# 2019_10_ELEV_18_IO.net
KiCad netlist of a schematic drawn in Altium Designer
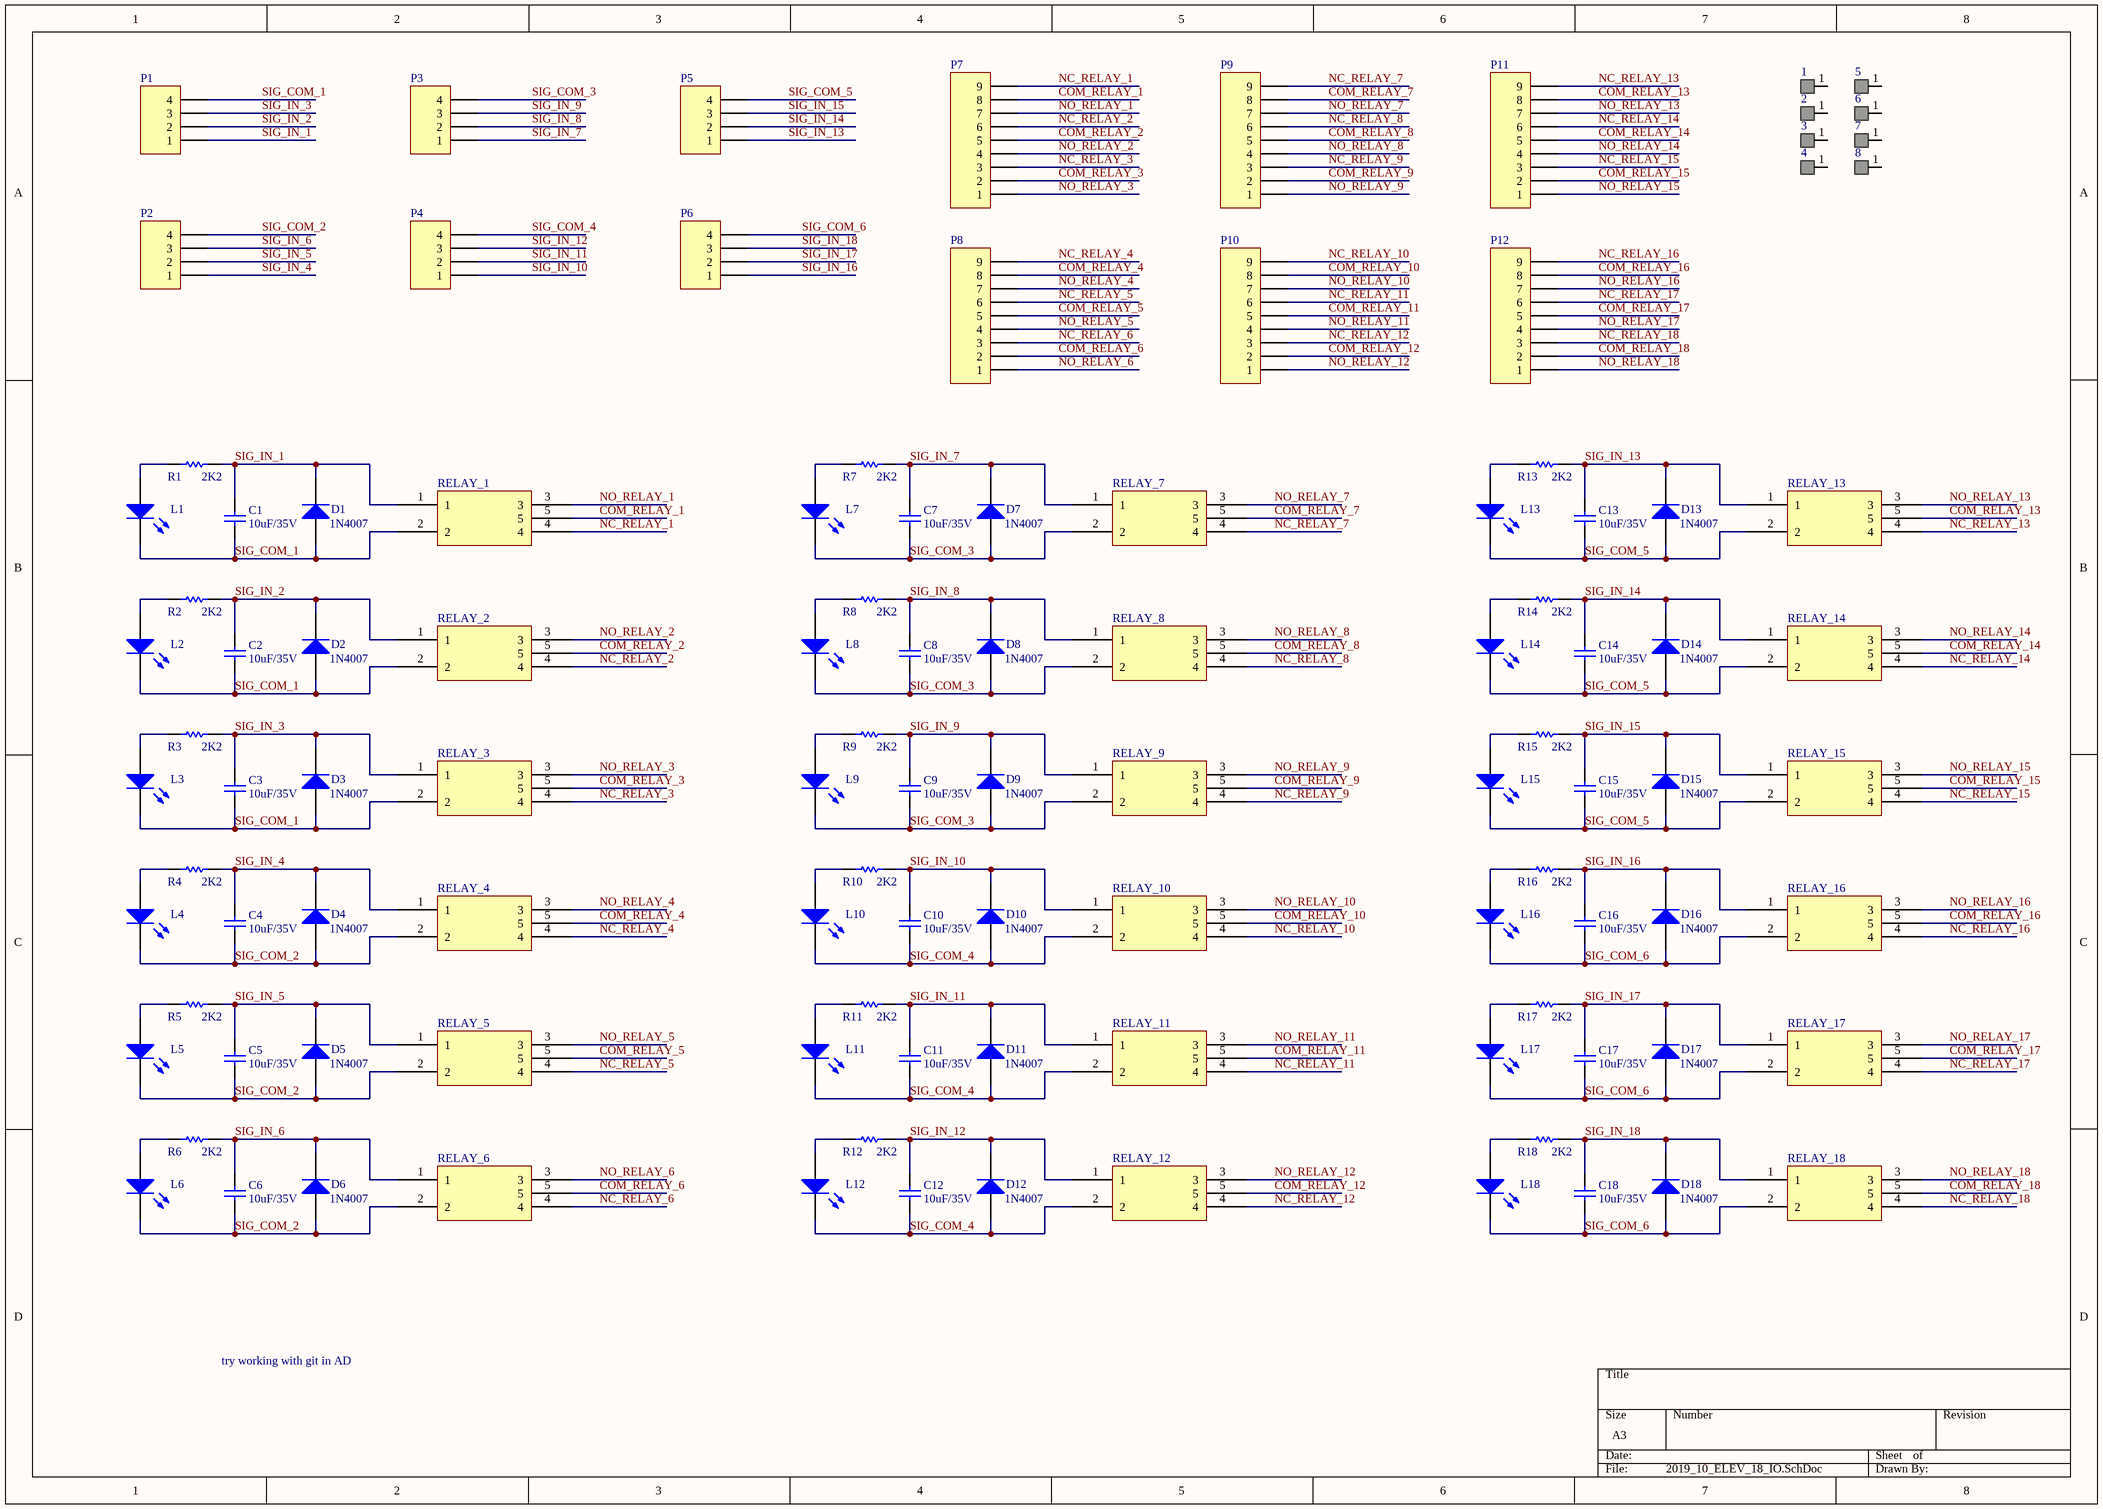
[diagram p0: 2019_10_ELEV_18_IO.SchDoc]

(export (version "E")
  (design (tool "Eeschema 10.0.6"))
  (components
    (comp (ref "1")
      (value "LOVIT_1")
      (footprint "VIT")
      (libsource (lib "2019_10_ELEV_18_IO") (part "LOVIT_1"))
    )
    (comp (ref "2")
      (value "LOVIT_1")
      (footprint "VIT")
      (libsource (lib "2019_10_ELEV_18_IO") (part "LOVIT_1"))
    )
    (comp (ref "3")
      (value "LOVIT_1")
      (footprint "VIT")
      (libsource (lib "2019_10_ELEV_18_IO") (part "LOVIT_1"))
    )
    (comp (ref "4")
      (value "LOVIT_1")
      (footprint "VIT")
      (libsource (lib "2019_10_ELEV_18_IO") (part "LOVIT_1"))
    )
    (comp (ref "5")
      (value "LOVIT_1")
      (footprint "VIT")
      (libsource (lib "2019_10_ELEV_18_IO") (part "LOVIT_1"))
    )
    (comp (ref "6")
      (value "LOVIT_1")
      (footprint "VIT")
      (libsource (lib "2019_10_ELEV_18_IO") (part "LOVIT_1"))
    )
    (comp (ref "7")
      (value "LOVIT_1")
      (footprint "VIT")
      (libsource (lib "2019_10_ELEV_18_IO") (part "LOVIT_1"))
    )
    (comp (ref "8")
      (value "LOVIT_1")
      (footprint "VIT")
      (libsource (lib "2019_10_ELEV_18_IO") (part "LOVIT_1"))
    )
    (comp (ref "C1")
      (value "10uF/35V")
      (footprint "C1210C106M6PACTU")
      (description "Multilayer Ceramic Capacitors MLCC - SMD/SMT 35V 10uF X5R 1210 20%")
      (fields (field (name "Comment") "Capacitor"))
      (libsource (lib "ICENTER_V3_2019_SCHLIB") (part "C1210C106M6PAC"))
    )
    (comp (ref "C2")
      (value "10uF/35V")
      (footprint "C1210C106M6PACTU")
      (description "Multilayer Ceramic Capacitors MLCC - SMD/SMT 35V 10uF X5R 1210 20%")
      (fields (field (name "Comment") "Capacitor"))
      (libsource (lib "ICENTER_V3_2019_SCHLIB") (part "C1210C106M6PAC"))
    )
    (comp (ref "C3")
      (value "10uF/35V")
      (footprint "C1210C106M6PACTU")
      (description "Multilayer Ceramic Capacitors MLCC - SMD/SMT 35V 10uF X5R 1210 20%")
      (fields (field (name "Comment") "Capacitor"))
      (libsource (lib "ICENTER_V3_2019_SCHLIB") (part "C1210C106M6PAC"))
    )
    (comp (ref "C4")
      (value "10uF/35V")
      (footprint "C1210C106M6PACTU")
      (description "Multilayer Ceramic Capacitors MLCC - SMD/SMT 35V 10uF X5R 1210 20%")
      (fields (field (name "Comment") "Capacitor"))
      (libsource (lib "ICENTER_V3_2019_SCHLIB") (part "C1210C106M6PAC"))
    )
    (comp (ref "C5")
      (value "10uF/35V")
      (footprint "C1210C106M6PACTU")
      (description "Multilayer Ceramic Capacitors MLCC - SMD/SMT 35V 10uF X5R 1210 20%")
      (fields (field (name "Comment") "Capacitor"))
      (libsource (lib "ICENTER_V3_2019_SCHLIB") (part "C1210C106M6PAC"))
    )
    (comp (ref "C6")
      (value "10uF/35V")
      (footprint "C1210C106M6PACTU")
      (description "Multilayer Ceramic Capacitors MLCC - SMD/SMT 35V 10uF X5R 1210 20%")
      (fields (field (name "Comment") "Capacitor"))
      (libsource (lib "ICENTER_V3_2019_SCHLIB") (part "C1210C106M6PAC"))
    )
    (comp (ref "C7")
      (value "10uF/35V")
      (footprint "C1210C106M6PACTU")
      (description "Multilayer Ceramic Capacitors MLCC - SMD/SMT 35V 10uF X5R 1210 20%")
      (fields (field (name "Comment") "Capacitor"))
      (libsource (lib "ICENTER_V3_2019_SCHLIB") (part "C1210C106M6PAC"))
    )
    (comp (ref "C8")
      (value "10uF/35V")
      (footprint "C1210C106M6PACTU")
      (description "Multilayer Ceramic Capacitors MLCC - SMD/SMT 35V 10uF X5R 1210 20%")
      (fields (field (name "Comment") "Capacitor"))
      (libsource (lib "ICENTER_V3_2019_SCHLIB") (part "C1210C106M6PAC"))
    )
    (comp (ref "C9")
      (value "10uF/35V")
      (footprint "C1210C106M6PACTU")
      (description "Multilayer Ceramic Capacitors MLCC - SMD/SMT 35V 10uF X5R 1210 20%")
      (fields (field (name "Comment") "Capacitor"))
      (libsource (lib "ICENTER_V3_2019_SCHLIB") (part "C1210C106M6PAC"))
    )
    (comp (ref "C10")
      (value "10uF/35V")
      (footprint "C1210C106M6PACTU")
      (description "Multilayer Ceramic Capacitors MLCC - SMD/SMT 35V 10uF X5R 1210 20%")
      (fields (field (name "Comment") "Capacitor"))
      (libsource (lib "ICENTER_V3_2019_SCHLIB") (part "C1210C106M6PAC"))
    )
    (comp (ref "C11")
      (value "10uF/35V")
      (footprint "C1210C106M6PACTU")
      (description "Multilayer Ceramic Capacitors MLCC - SMD/SMT 35V 10uF X5R 1210 20%")
      (fields (field (name "Comment") "Capacitor"))
      (libsource (lib "ICENTER_V3_2019_SCHLIB") (part "C1210C106M6PAC"))
    )
    (comp (ref "C12")
      (value "10uF/35V")
      (footprint "C1210C106M6PACTU")
      (description "Multilayer Ceramic Capacitors MLCC - SMD/SMT 35V 10uF X5R 1210 20%")
      (fields (field (name "Comment") "Capacitor"))
      (libsource (lib "ICENTER_V3_2019_SCHLIB") (part "C1210C106M6PAC"))
    )
    (comp (ref "C13")
      (value "10uF/35V")
      (footprint "C1210C106M6PACTU")
      (description "Multilayer Ceramic Capacitors MLCC - SMD/SMT 35V 10uF X5R 1210 20%")
      (fields (field (name "Comment") "Capacitor"))
      (libsource (lib "ICENTER_V3_2019_SCHLIB") (part "C1210C106M6PAC"))
    )
    (comp (ref "C14")
      (value "10uF/35V")
      (footprint "C1210C106M6PACTU")
      (description "Multilayer Ceramic Capacitors MLCC - SMD/SMT 35V 10uF X5R 1210 20%")
      (fields (field (name "Comment") "Capacitor"))
      (libsource (lib "ICENTER_V3_2019_SCHLIB") (part "C1210C106M6PAC"))
    )
    (comp (ref "C15")
      (value "10uF/35V")
      (footprint "C1210C106M6PACTU")
      (description "Multilayer Ceramic Capacitors MLCC - SMD/SMT 35V 10uF X5R 1210 20%")
      (fields (field (name "Comment") "Capacitor"))
      (libsource (lib "ICENTER_V3_2019_SCHLIB") (part "C1210C106M6PAC"))
    )
    (comp (ref "C16")
      (value "10uF/35V")
      (footprint "C1210C106M6PACTU")
      (description "Multilayer Ceramic Capacitors MLCC - SMD/SMT 35V 10uF X5R 1210 20%")
      (fields (field (name "Comment") "Capacitor"))
      (libsource (lib "ICENTER_V3_2019_SCHLIB") (part "C1210C106M6PAC"))
    )
    (comp (ref "C17")
      (value "10uF/35V")
      (footprint "C1210C106M6PACTU")
      (description "Multilayer Ceramic Capacitors MLCC - SMD/SMT 35V 10uF X5R 1210 20%")
      (fields (field (name "Comment") "Capacitor"))
      (libsource (lib "ICENTER_V3_2019_SCHLIB") (part "C1210C106M6PAC"))
    )
    (comp (ref "C18")
      (value "10uF/35V")
      (footprint "C1210C106M6PACTU")
      (description "Multilayer Ceramic Capacitors MLCC - SMD/SMT 35V 10uF X5R 1210 20%")
      (fields (field (name "Comment") "Capacitor"))
      (libsource (lib "ICENTER_V3_2019_SCHLIB") (part "C1210C106M6PAC"))
    )
    (comp (ref "D1")
      (value "1N4007")
      (footprint "DO-214AC")
      (description "Diode Rectifiers 1.5 Amp 1000 Volt")
      (libsource (lib "ICENTER_V3_2019_SCHLIB") (part "BYG21M-E3/TR"))
    )
    (comp (ref "D2")
      (value "1N4007")
      (footprint "DO-214AC")
      (description "Diode Rectifiers 1.5 Amp 1000 Volt")
      (libsource (lib "ICENTER_V3_2019_SCHLIB") (part "BYG21M-E3/TR"))
    )
    (comp (ref "D3")
      (value "1N4007")
      (footprint "DO-214AC")
      (description "Diode Rectifiers 1.5 Amp 1000 Volt")
      (libsource (lib "ICENTER_V3_2019_SCHLIB") (part "BYG21M-E3/TR"))
    )
    (comp (ref "D4")
      (value "1N4007")
      (footprint "DO-214AC")
      (description "Diode Rectifiers 1.5 Amp 1000 Volt")
      (libsource (lib "ICENTER_V3_2019_SCHLIB") (part "BYG21M-E3/TR"))
    )
    (comp (ref "D5")
      (value "1N4007")
      (footprint "DO-214AC")
      (description "Diode Rectifiers 1.5 Amp 1000 Volt")
      (libsource (lib "ICENTER_V3_2019_SCHLIB") (part "BYG21M-E3/TR"))
    )
    (comp (ref "D6")
      (value "1N4007")
      (footprint "DO-214AC")
      (description "Diode Rectifiers 1.5 Amp 1000 Volt")
      (libsource (lib "ICENTER_V3_2019_SCHLIB") (part "BYG21M-E3/TR"))
    )
    (comp (ref "D7")
      (value "1N4007")
      (footprint "DO-214AC")
      (description "Diode Rectifiers 1.5 Amp 1000 Volt")
      (libsource (lib "ICENTER_V3_2019_SCHLIB") (part "BYG21M-E3/TR"))
    )
    (comp (ref "D8")
      (value "1N4007")
      (footprint "DO-214AC")
      (description "Diode Rectifiers 1.5 Amp 1000 Volt")
      (libsource (lib "ICENTER_V3_2019_SCHLIB") (part "BYG21M-E3/TR"))
    )
    (comp (ref "D9")
      (value "1N4007")
      (footprint "DO-214AC")
      (description "Diode Rectifiers 1.5 Amp 1000 Volt")
      (libsource (lib "ICENTER_V3_2019_SCHLIB") (part "BYG21M-E3/TR"))
    )
    (comp (ref "D10")
      (value "1N4007")
      (footprint "DO-214AC")
      (description "Diode Rectifiers 1.5 Amp 1000 Volt")
      (libsource (lib "ICENTER_V3_2019_SCHLIB") (part "BYG21M-E3/TR"))
    )
    (comp (ref "D11")
      (value "1N4007")
      (footprint "DO-214AC")
      (description "Diode Rectifiers 1.5 Amp 1000 Volt")
      (libsource (lib "ICENTER_V3_2019_SCHLIB") (part "BYG21M-E3/TR"))
    )
    (comp (ref "D12")
      (value "1N4007")
      (footprint "DO-214AC")
      (description "Diode Rectifiers 1.5 Amp 1000 Volt")
      (libsource (lib "ICENTER_V3_2019_SCHLIB") (part "BYG21M-E3/TR"))
    )
    (comp (ref "D13")
      (value "1N4007")
      (footprint "DO-214AC")
      (description "Diode Rectifiers 1.5 Amp 1000 Volt")
      (libsource (lib "ICENTER_V3_2019_SCHLIB") (part "BYG21M-E3/TR"))
    )
    (comp (ref "D14")
      (value "1N4007")
      (footprint "DO-214AC")
      (description "Diode Rectifiers 1.5 Amp 1000 Volt")
      (libsource (lib "ICENTER_V3_2019_SCHLIB") (part "BYG21M-E3/TR"))
    )
    (comp (ref "D15")
      (value "1N4007")
      (footprint "DO-214AC")
      (description "Diode Rectifiers 1.5 Amp 1000 Volt")
      (libsource (lib "ICENTER_V3_2019_SCHLIB") (part "BYG21M-E3/TR"))
    )
    (comp (ref "D16")
      (value "1N4007")
      (footprint "DO-214AC")
      (description "Diode Rectifiers 1.5 Amp 1000 Volt")
      (libsource (lib "ICENTER_V3_2019_SCHLIB") (part "BYG21M-E3/TR"))
    )
    (comp (ref "D17")
      (value "1N4007")
      (footprint "DO-214AC")
      (description "Diode Rectifiers 1.5 Amp 1000 Volt")
      (libsource (lib "ICENTER_V3_2019_SCHLIB") (part "BYG21M-E3/TR"))
    )
    (comp (ref "D18")
      (value "1N4007")
      (footprint "DO-214AC")
      (description "Diode Rectifiers 1.5 Amp 1000 Volt")
      (libsource (lib "ICENTER_V3_2019_SCHLIB") (part "BYG21M-E3/TR"))
    )
    (comp (ref "L1")
      (value "LED0")
      (footprint "LED_3MM")
      (description "Typical INFRARED GaAs LED")
      (fields (field (name "PUBLISHER") "Altium Limited"))
      (libsource (lib "Miscellaneous Devices") (part "LED0"))
    )
    (comp (ref "L2")
      (value "LED0")
      (footprint "LED_3MM")
      (description "Typical INFRARED GaAs LED")
      (fields (field (name "PUBLISHER") "Altium Limited"))
      (libsource (lib "Miscellaneous Devices") (part "LED0"))
    )
    (comp (ref "L3")
      (value "LED0")
      (footprint "LED_3MM")
      (description "Typical INFRARED GaAs LED")
      (fields (field (name "PUBLISHER") "Altium Limited"))
      (libsource (lib "Miscellaneous Devices") (part "LED0"))
    )
    (comp (ref "L4")
      (value "LED0")
      (footprint "LED_3MM")
      (description "Typical INFRARED GaAs LED")
      (fields (field (name "PUBLISHER") "Altium Limited"))
      (libsource (lib "Miscellaneous Devices") (part "LED0"))
    )
    (comp (ref "L5")
      (value "LED0")
      (footprint "LED_3MM")
      (description "Typical INFRARED GaAs LED")
      (fields (field (name "PUBLISHER") "Altium Limited"))
      (libsource (lib "Miscellaneous Devices") (part "LED0"))
    )
    (comp (ref "L6")
      (value "LED0")
      (footprint "LED_3MM")
      (description "Typical INFRARED GaAs LED")
      (fields (field (name "PUBLISHER") "Altium Limited"))
      (libsource (lib "Miscellaneous Devices") (part "LED0"))
    )
    (comp (ref "L7")
      (value "LED0")
      (footprint "LED_3MM")
      (description "Typical INFRARED GaAs LED")
      (fields (field (name "PUBLISHER") "Altium Limited"))
      (libsource (lib "Miscellaneous Devices") (part "LED0"))
    )
    (comp (ref "L8")
      (value "LED0")
      (footprint "LED_3MM")
      (description "Typical INFRARED GaAs LED")
      (fields (field (name "PUBLISHER") "Altium Limited"))
      (libsource (lib "Miscellaneous Devices") (part "LED0"))
    )
    (comp (ref "L9")
      (value "LED0")
      (footprint "LED_3MM")
      (description "Typical INFRARED GaAs LED")
      (fields (field (name "PUBLISHER") "Altium Limited"))
      (libsource (lib "Miscellaneous Devices") (part "LED0"))
    )
    (comp (ref "L10")
      (value "LED0")
      (footprint "LED_3MM")
      (description "Typical INFRARED GaAs LED")
      (fields (field (name "PUBLISHER") "Altium Limited"))
      (libsource (lib "Miscellaneous Devices") (part "LED0"))
    )
    (comp (ref "L11")
      (value "LED0")
      (footprint "LED_3MM")
      (description "Typical INFRARED GaAs LED")
      (fields (field (name "PUBLISHER") "Altium Limited"))
      (libsource (lib "Miscellaneous Devices") (part "LED0"))
    )
    (comp (ref "L12")
      (value "LED0")
      (footprint "LED_3MM")
      (description "Typical INFRARED GaAs LED")
      (fields (field (name "PUBLISHER") "Altium Limited"))
      (libsource (lib "Miscellaneous Devices") (part "LED0"))
    )
    (comp (ref "L13")
      (value "LED0")
      (footprint "LED_3MM")
      (description "Typical INFRARED GaAs LED")
      (fields (field (name "PUBLISHER") "Altium Limited"))
      (libsource (lib "Miscellaneous Devices") (part "LED0"))
    )
    (comp (ref "L14")
      (value "LED0")
      (footprint "LED_3MM")
      (description "Typical INFRARED GaAs LED")
      (fields (field (name "PUBLISHER") "Altium Limited"))
      (libsource (lib "Miscellaneous Devices") (part "LED0"))
    )
    (comp (ref "L15")
      (value "LED0")
      (footprint "LED_3MM")
      (description "Typical INFRARED GaAs LED")
      (fields (field (name "PUBLISHER") "Altium Limited"))
      (libsource (lib "Miscellaneous Devices") (part "LED0"))
    )
    (comp (ref "L16")
      (value "LED0")
      (footprint "LED_3MM")
      (description "Typical INFRARED GaAs LED")
      (fields (field (name "PUBLISHER") "Altium Limited"))
      (libsource (lib "Miscellaneous Devices") (part "LED0"))
    )
    (comp (ref "L17")
      (value "LED0")
      (footprint "LED_3MM")
      (description "Typical INFRARED GaAs LED")
      (fields (field (name "PUBLISHER") "Altium Limited"))
      (libsource (lib "Miscellaneous Devices") (part "LED0"))
    )
    (comp (ref "L18")
      (value "LED0")
      (footprint "LED_3MM")
      (description "Typical INFRARED GaAs LED")
      (fields (field (name "PUBLISHER") "Altium Limited"))
      (libsource (lib "Miscellaneous Devices") (part "LED0"))
    )
    (comp (ref "P1")
      (value "Header 4")
      (footprint "TERMINAL_4PIN_381MM")
      (description "Header, 4-Pin")
      (fields (field (name "PUBLISHER") "Altium Limited"))
      (libsource (lib "Miscellaneous Connectors") (part "Header 4"))
    )
    (comp (ref "P2")
      (value "Header 4")
      (footprint "TERMINAL_4PIN_381MM")
      (description "Header, 4-Pin")
      (fields (field (name "PUBLISHER") "Altium Limited"))
      (libsource (lib "Miscellaneous Connectors") (part "Header 4"))
    )
    (comp (ref "P3")
      (value "Header 4")
      (footprint "TERMINAL_4PIN_381MM")
      (description "Header, 4-Pin")
      (fields (field (name "PUBLISHER") "Altium Limited"))
      (libsource (lib "Miscellaneous Connectors") (part "Header 4"))
    )
    (comp (ref "P4")
      (value "Header 4")
      (footprint "TERMINAL_4PIN_381MM")
      (description "Header, 4-Pin")
      (fields (field (name "PUBLISHER") "Altium Limited"))
      (libsource (lib "Miscellaneous Connectors") (part "Header 4"))
    )
    (comp (ref "P5")
      (value "Header 4")
      (footprint "TERMINAL_4PIN_381MM")
      (description "Header, 4-Pin")
      (fields (field (name "PUBLISHER") "Altium Limited"))
      (libsource (lib "Miscellaneous Connectors") (part "Header 4"))
    )
    (comp (ref "P6")
      (value "Header 4")
      (footprint "TERMINAL_4PIN_381MM")
      (description "Header, 4-Pin")
      (fields (field (name "PUBLISHER") "Altium Limited"))
      (libsource (lib "Miscellaneous Connectors") (part "Header 4"))
    )
    (comp (ref "P7")
      (value "Header 9")
      (footprint "TERMINAL_6PIN_381MM")
      (description "Header, 9-Pin")
      (fields (field (name "PUBLISHER") "Altium Limited"))
      (libsource (lib "Miscellaneous Connectors") (part "Header 9"))
    )
    (comp (ref "P8")
      (value "Header 9")
      (footprint "TERMINAL_6PIN_381MM")
      (description "Header, 9-Pin")
      (fields (field (name "PUBLISHER") "Altium Limited"))
      (libsource (lib "Miscellaneous Connectors") (part "Header 9"))
    )
    (comp (ref "P9")
      (value "Header 9")
      (footprint "TERMINAL_6PIN_381MM")
      (description "Header, 9-Pin")
      (fields (field (name "PUBLISHER") "Altium Limited"))
      (libsource (lib "Miscellaneous Connectors") (part "Header 9"))
    )
    (comp (ref "P10")
      (value "Header 9")
      (footprint "TERMINAL_6PIN_381MM")
      (description "Header, 9-Pin")
      (fields (field (name "PUBLISHER") "Altium Limited"))
      (libsource (lib "Miscellaneous Connectors") (part "Header 9"))
    )
    (comp (ref "P11")
      (value "Header 9")
      (footprint "TERMINAL_6PIN_381MM")
      (description "Header, 9-Pin")
      (fields (field (name "PUBLISHER") "Altium Limited"))
      (libsource (lib "Miscellaneous Connectors") (part "Header 9"))
    )
    (comp (ref "P12")
      (value "Header 9")
      (footprint "TERMINAL_6PIN_381MM")
      (description "Header, 9-Pin")
      (fields (field (name "PUBLISHER") "Altium Limited"))
      (libsource (lib "Miscellaneous Connectors") (part "Header 9"))
    )
    (comp (ref "R1")
      (value "2K2")
      (footprint "CRCW080510K0FKEAC")
      (description "Thick Film Resistors - SMD 1K OHM 5%")
      (fields (field (name "Comment") "Resistor"))
      (libsource (lib "ICENTER_V3_2019_SCHLIB") (part "RC0805JR-131KL"))
    )
    (comp (ref "R2")
      (value "2K2")
      (footprint "CRCW080510K0FKEAC")
      (description "Thick Film Resistors - SMD 1K OHM 5%")
      (fields (field (name "Comment") "Resistor"))
      (libsource (lib "ICENTER_V3_2019_SCHLIB") (part "RC0805JR-131KL"))
    )
    (comp (ref "R3")
      (value "2K2")
      (footprint "CRCW080510K0FKEAC")
      (description "Thick Film Resistors - SMD 1K OHM 5%")
      (fields (field (name "Comment") "Resistor"))
      (libsource (lib "ICENTER_V3_2019_SCHLIB") (part "RC0805JR-131KL"))
    )
    (comp (ref "R4")
      (value "2K2")
      (footprint "CRCW080510K0FKEAC")
      (description "Thick Film Resistors - SMD 1K OHM 5%")
      (fields (field (name "Comment") "Resistor"))
      (libsource (lib "ICENTER_V3_2019_SCHLIB") (part "RC0805JR-131KL"))
    )
    (comp (ref "R5")
      (value "2K2")
      (footprint "CRCW080510K0FKEAC")
      (description "Thick Film Resistors - SMD 1K OHM 5%")
      (fields (field (name "Comment") "Resistor"))
      (libsource (lib "ICENTER_V3_2019_SCHLIB") (part "RC0805JR-131KL"))
    )
    (comp (ref "R6")
      (value "2K2")
      (footprint "CRCW080510K0FKEAC")
      (description "Thick Film Resistors - SMD 1K OHM 5%")
      (fields (field (name "Comment") "Resistor"))
      (libsource (lib "ICENTER_V3_2019_SCHLIB") (part "RC0805JR-131KL"))
    )
    (comp (ref "R7")
      (value "2K2")
      (footprint "CRCW080510K0FKEAC")
      (description "Thick Film Resistors - SMD 1K OHM 5%")
      (fields (field (name "Comment") "Resistor"))
      (libsource (lib "ICENTER_V3_2019_SCHLIB") (part "RC0805JR-131KL"))
    )
    (comp (ref "R8")
      (value "2K2")
      (footprint "CRCW080510K0FKEAC")
      (description "Thick Film Resistors - SMD 1K OHM 5%")
      (fields (field (name "Comment") "Resistor"))
      (libsource (lib "ICENTER_V3_2019_SCHLIB") (part "RC0805JR-131KL"))
    )
    (comp (ref "R9")
      (value "2K2")
      (footprint "CRCW080510K0FKEAC")
      (description "Thick Film Resistors - SMD 1K OHM 5%")
      (fields (field (name "Comment") "Resistor"))
      (libsource (lib "ICENTER_V3_2019_SCHLIB") (part "RC0805JR-131KL"))
    )
    (comp (ref "R10")
      (value "2K2")
      (footprint "CRCW080510K0FKEAC")
      (description "Thick Film Resistors - SMD 1K OHM 5%")
      (fields (field (name "Comment") "Resistor"))
      (libsource (lib "ICENTER_V3_2019_SCHLIB") (part "RC0805JR-131KL"))
    )
    (comp (ref "R11")
      (value "2K2")
      (footprint "CRCW080510K0FKEAC")
      (description "Thick Film Resistors - SMD 1K OHM 5%")
      (fields (field (name "Comment") "Resistor"))
      (libsource (lib "ICENTER_V3_2019_SCHLIB") (part "RC0805JR-131KL"))
    )
    (comp (ref "R12")
      (value "2K2")
      (footprint "CRCW080510K0FKEAC")
      (description "Thick Film Resistors - SMD 1K OHM 5%")
      (fields (field (name "Comment") "Resistor"))
      (libsource (lib "ICENTER_V3_2019_SCHLIB") (part "RC0805JR-131KL"))
    )
    (comp (ref "R13")
      (value "2K2")
      (footprint "CRCW080510K0FKEAC")
      (description "Thick Film Resistors - SMD 1K OHM 5%")
      (fields (field (name "Comment") "Resistor"))
      (libsource (lib "ICENTER_V3_2019_SCHLIB") (part "RC0805JR-131KL"))
    )
    (comp (ref "R14")
      (value "2K2")
      (footprint "CRCW080510K0FKEAC")
      (description "Thick Film Resistors - SMD 1K OHM 5%")
      (fields (field (name "Comment") "Resistor"))
      (libsource (lib "ICENTER_V3_2019_SCHLIB") (part "RC0805JR-131KL"))
    )
    (comp (ref "R15")
      (value "2K2")
      (footprint "CRCW080510K0FKEAC")
      (description "Thick Film Resistors - SMD 1K OHM 5%")
      (fields (field (name "Comment") "Resistor"))
      (libsource (lib "ICENTER_V3_2019_SCHLIB") (part "RC0805JR-131KL"))
    )
    (comp (ref "R16")
      (value "2K2")
      (footprint "CRCW080510K0FKEAC")
      (description "Thick Film Resistors - SMD 1K OHM 5%")
      (fields (field (name "Comment") "Resistor"))
      (libsource (lib "ICENTER_V3_2019_SCHLIB") (part "RC0805JR-131KL"))
    )
    (comp (ref "R17")
      (value "2K2")
      (footprint "CRCW080510K0FKEAC")
      (description "Thick Film Resistors - SMD 1K OHM 5%")
      (fields (field (name "Comment") "Resistor"))
      (libsource (lib "ICENTER_V3_2019_SCHLIB") (part "RC0805JR-131KL"))
    )
    (comp (ref "R18")
      (value "2K2")
      (footprint "CRCW080510K0FKEAC")
      (description "Thick Film Resistors - SMD 1K OHM 5%")
      (fields (field (name "Comment") "Resistor"))
      (libsource (lib "ICENTER_V3_2019_SCHLIB") (part "RC0805JR-131KL"))
    )
    (comp (ref "RELAY_1")
      (value "Component_1")
      (footprint "RELAY_JS1-24V-F")
      (libsource (lib "altium-import") (part "root_0_Component_1_"))
    )
    (comp (ref "RELAY_2")
      (value "Component_1")
      (footprint "RELAY_JS1-24V-F")
      (libsource (lib "altium-import") (part "root_0_Component_1_"))
    )
    (comp (ref "RELAY_3")
      (value "Component_1")
      (footprint "RELAY_JS1-24V-F")
      (libsource (lib "altium-import") (part "root_0_Component_1_"))
    )
    (comp (ref "RELAY_4")
      (value "Component_1")
      (footprint "RELAY_JS1-24V-F")
      (libsource (lib "altium-import") (part "root_0_Component_1_"))
    )
    (comp (ref "RELAY_5")
      (value "Component_1")
      (footprint "RELAY_JS1-24V-F")
      (libsource (lib "altium-import") (part "root_0_Component_1_"))
    )
    (comp (ref "RELAY_6")
      (value "Component_1")
      (footprint "RELAY_JS1-24V-F")
      (libsource (lib "altium-import") (part "root_0_Component_1_"))
    )
    (comp (ref "RELAY_7")
      (value "Component_1")
      (footprint "RELAY_JS1-24V-F")
      (libsource (lib "altium-import") (part "root_0_Component_1_"))
    )
    (comp (ref "RELAY_8")
      (value "Component_1")
      (footprint "RELAY_JS1-24V-F")
      (libsource (lib "altium-import") (part "root_0_Component_1_"))
    )
    (comp (ref "RELAY_9")
      (value "Component_1")
      (footprint "RELAY_JS1-24V-F")
      (libsource (lib "altium-import") (part "root_0_Component_1_"))
    )
    (comp (ref "RELAY_10")
      (value "Component_1")
      (footprint "RELAY_JS1-24V-F")
      (libsource (lib "altium-import") (part "root_0_Component_1_"))
    )
    (comp (ref "RELAY_11")
      (value "Component_1")
      (footprint "RELAY_JS1-24V-F")
      (libsource (lib "altium-import") (part "root_0_Component_1_"))
    )
    (comp (ref "RELAY_12")
      (value "Component_1")
      (footprint "RELAY_JS1-24V-F")
      (libsource (lib "altium-import") (part "root_0_Component_1_"))
    )
    (comp (ref "RELAY_13")
      (value "Component_1")
      (footprint "RELAY_JS1-24V-F")
      (libsource (lib "altium-import") (part "root_0_Component_1_"))
    )
    (comp (ref "RELAY_14")
      (value "Component_1")
      (footprint "RELAY_JS1-24V-F")
      (libsource (lib "altium-import") (part "root_0_Component_1_"))
    )
    (comp (ref "RELAY_15")
      (value "Component_1")
      (footprint "RELAY_JS1-24V-F")
      (libsource (lib "altium-import") (part "root_0_Component_1_"))
    )
    (comp (ref "RELAY_16")
      (value "Component_1")
      (footprint "RELAY_JS1-24V-F")
      (libsource (lib "altium-import") (part "root_0_Component_1_"))
    )
    (comp (ref "RELAY_17")
      (value "Component_1")
      (footprint "RELAY_JS1-24V-F")
      (libsource (lib "altium-import") (part "root_0_Component_1_"))
    )
    (comp (ref "RELAY_18")
      (value "Component_1")
      (footprint "RELAY_JS1-24V-F")
      (libsource (lib "altium-import") (part "root_0_Component_1_"))
    )
  )
  (nets
    (net (code "1") (name "/COM_RELAY_1") (class "Default")
      (node (ref "P7") (pin "8") (pinfunction "8_8") (pintype "passive"))
      (node (ref "RELAY_1") (pin "5") (pinfunction "5_5") (pintype "passive"))
    )
    (net (code "2") (name "/COM_RELAY_2") (class "Default")
      (node (ref "P7") (pin "5") (pinfunction "5_5") (pintype "passive"))
      (node (ref "RELAY_2") (pin "5") (pinfunction "5_5") (pintype "passive"))
    )
    (net (code "3") (name "/COM_RELAY_3") (class "Default")
      (node (ref "P7") (pin "2") (pinfunction "2_2") (pintype "passive"))
      (node (ref "RELAY_3") (pin "5") (pinfunction "5_5") (pintype "passive"))
    )
    (net (code "4") (name "/COM_RELAY_4") (class "Default")
      (node (ref "P8") (pin "8") (pinfunction "8_8") (pintype "passive"))
      (node (ref "RELAY_4") (pin "5") (pinfunction "5_5") (pintype "passive"))
    )
    (net (code "5") (name "/COM_RELAY_5") (class "Default")
      (node (ref "P8") (pin "5") (pinfunction "5_5") (pintype "passive"))
      (node (ref "RELAY_5") (pin "5") (pinfunction "5_5") (pintype "passive"))
    )
    (net (code "6") (name "/COM_RELAY_6") (class "Default")
      (node (ref "P8") (pin "2") (pinfunction "2_2") (pintype "passive"))
      (node (ref "RELAY_6") (pin "5") (pinfunction "5_5") (pintype "passive"))
    )
    (net (code "7") (name "/COM_RELAY_7") (class "Default")
      (node (ref "P9") (pin "8") (pinfunction "8_8") (pintype "passive"))
      (node (ref "RELAY_7") (pin "5") (pinfunction "5_5") (pintype "passive"))
    )
    (net (code "8") (name "/COM_RELAY_8") (class "Default")
      (node (ref "P9") (pin "5") (pinfunction "5_5") (pintype "passive"))
      (node (ref "RELAY_8") (pin "5") (pinfunction "5_5") (pintype "passive"))
    )
    (net (code "9") (name "/COM_RELAY_9") (class "Default")
      (node (ref "P9") (pin "2") (pinfunction "2_2") (pintype "passive"))
      (node (ref "RELAY_9") (pin "5") (pinfunction "5_5") (pintype "passive"))
    )
    (net (code "10") (name "/COM_RELAY_10") (class "Default")
      (node (ref "P10") (pin "8") (pinfunction "8_8") (pintype "passive"))
      (node (ref "RELAY_10") (pin "5") (pinfunction "5_5") (pintype "passive"))
    )
    (net (code "11") (name "/COM_RELAY_11") (class "Default")
      (node (ref "P10") (pin "5") (pinfunction "5_5") (pintype "passive"))
      (node (ref "RELAY_11") (pin "5") (pinfunction "5_5") (pintype "passive"))
    )
    (net (code "12") (name "/COM_RELAY_12") (class "Default")
      (node (ref "P10") (pin "2") (pinfunction "2_2") (pintype "passive"))
      (node (ref "RELAY_12") (pin "5") (pinfunction "5_5") (pintype "passive"))
    )
    (net (code "13") (name "/COM_RELAY_13") (class "Default")
      (node (ref "P11") (pin "8") (pinfunction "8_8") (pintype "passive"))
      (node (ref "RELAY_13") (pin "5") (pinfunction "5_5") (pintype "passive"))
    )
    (net (code "14") (name "/COM_RELAY_14") (class "Default")
      (node (ref "P11") (pin "5") (pinfunction "5_5") (pintype "passive"))
      (node (ref "RELAY_14") (pin "5") (pinfunction "5_5") (pintype "passive"))
    )
    (net (code "15") (name "/COM_RELAY_15") (class "Default")
      (node (ref "P11") (pin "2") (pinfunction "2_2") (pintype "passive"))
      (node (ref "RELAY_15") (pin "5") (pinfunction "5_5") (pintype "passive"))
    )
    (net (code "16") (name "/COM_RELAY_16") (class "Default")
      (node (ref "P12") (pin "8") (pinfunction "8_8") (pintype "passive"))
      (node (ref "RELAY_16") (pin "5") (pinfunction "5_5") (pintype "passive"))
    )
    (net (code "17") (name "/COM_RELAY_17") (class "Default")
      (node (ref "P12") (pin "5") (pinfunction "5_5") (pintype "passive"))
      (node (ref "RELAY_17") (pin "5") (pinfunction "5_5") (pintype "passive"))
    )
    (net (code "18") (name "/COM_RELAY_18") (class "Default")
      (node (ref "P12") (pin "2") (pinfunction "2_2") (pintype "passive"))
      (node (ref "RELAY_18") (pin "5") (pinfunction "5_5") (pintype "passive"))
    )
    (net (code "19") (name "/NC_RELAY_1") (class "Default")
      (node (ref "P7") (pin "9") (pinfunction "9_9") (pintype "passive"))
      (node (ref "RELAY_1") (pin "4") (pinfunction "4_4") (pintype "passive"))
    )
    (net (code "20") (name "/NC_RELAY_2") (class "Default")
      (node (ref "P7") (pin "6") (pinfunction "6_6") (pintype "passive"))
      (node (ref "RELAY_2") (pin "4") (pinfunction "4_4") (pintype "passive"))
    )
    (net (code "21") (name "/NC_RELAY_3") (class "Default")
      (node (ref "P7") (pin "3") (pinfunction "3_3") (pintype "passive"))
      (node (ref "RELAY_3") (pin "4") (pinfunction "4_4") (pintype "passive"))
    )
    (net (code "22") (name "/NC_RELAY_4") (class "Default")
      (node (ref "P8") (pin "9") (pinfunction "9_9") (pintype "passive"))
      (node (ref "RELAY_4") (pin "4") (pinfunction "4_4") (pintype "passive"))
    )
    (net (code "23") (name "/NC_RELAY_5") (class "Default")
      (node (ref "P8") (pin "6") (pinfunction "6_6") (pintype "passive"))
      (node (ref "RELAY_5") (pin "4") (pinfunction "4_4") (pintype "passive"))
    )
    (net (code "24") (name "/NC_RELAY_6") (class "Default")
      (node (ref "P8") (pin "3") (pinfunction "3_3") (pintype "passive"))
      (node (ref "RELAY_6") (pin "4") (pinfunction "4_4") (pintype "passive"))
    )
    (net (code "25") (name "/NC_RELAY_7") (class "Default")
      (node (ref "P9") (pin "9") (pinfunction "9_9") (pintype "passive"))
      (node (ref "RELAY_7") (pin "4") (pinfunction "4_4") (pintype "passive"))
    )
    (net (code "26") (name "/NC_RELAY_8") (class "Default")
      (node (ref "P9") (pin "6") (pinfunction "6_6") (pintype "passive"))
      (node (ref "RELAY_8") (pin "4") (pinfunction "4_4") (pintype "passive"))
    )
    (net (code "27") (name "/NC_RELAY_9") (class "Default")
      (node (ref "P9") (pin "3") (pinfunction "3_3") (pintype "passive"))
      (node (ref "RELAY_9") (pin "4") (pinfunction "4_4") (pintype "passive"))
    )
    (net (code "28") (name "/NC_RELAY_10") (class "Default")
      (node (ref "P10") (pin "9") (pinfunction "9_9") (pintype "passive"))
      (node (ref "RELAY_10") (pin "4") (pinfunction "4_4") (pintype "passive"))
    )
    (net (code "29") (name "/NC_RELAY_11") (class "Default")
      (node (ref "P10") (pin "6") (pinfunction "6_6") (pintype "passive"))
      (node (ref "RELAY_11") (pin "4") (pinfunction "4_4") (pintype "passive"))
    )
    (net (code "30") (name "/NC_RELAY_12") (class "Default")
      (node (ref "P10") (pin "3") (pinfunction "3_3") (pintype "passive"))
      (node (ref "RELAY_12") (pin "4") (pinfunction "4_4") (pintype "passive"))
    )
    (net (code "31") (name "/NC_RELAY_13") (class "Default")
      (node (ref "P11") (pin "9") (pinfunction "9_9") (pintype "passive"))
      (node (ref "RELAY_13") (pin "4") (pinfunction "4_4") (pintype "passive"))
    )
    (net (code "32") (name "/NC_RELAY_14") (class "Default")
      (node (ref "P11") (pin "6") (pinfunction "6_6") (pintype "passive"))
      (node (ref "RELAY_14") (pin "4") (pinfunction "4_4") (pintype "passive"))
    )
    (net (code "33") (name "/NC_RELAY_15") (class "Default")
      (node (ref "P11") (pin "3") (pinfunction "3_3") (pintype "passive"))
      (node (ref "RELAY_15") (pin "4") (pinfunction "4_4") (pintype "passive"))
    )
    (net (code "34") (name "/NC_RELAY_16") (class "Default")
      (node (ref "P12") (pin "9") (pinfunction "9_9") (pintype "passive"))
      (node (ref "RELAY_16") (pin "4") (pinfunction "4_4") (pintype "passive"))
    )
    (net (code "35") (name "/NC_RELAY_17") (class "Default")
      (node (ref "P12") (pin "6") (pinfunction "6_6") (pintype "passive"))
      (node (ref "RELAY_17") (pin "4") (pinfunction "4_4") (pintype "passive"))
    )
    (net (code "36") (name "/NC_RELAY_18") (class "Default")
      (node (ref "P12") (pin "3") (pinfunction "3_3") (pintype "passive"))
      (node (ref "RELAY_18") (pin "4") (pinfunction "4_4") (pintype "passive"))
    )
    (net (code "37") (name "/NO_RELAY_1") (class "Default")
      (node (ref "P7") (pin "7") (pinfunction "7_7") (pintype "passive"))
      (node (ref "RELAY_1") (pin "3") (pinfunction "3_3") (pintype "passive"))
    )
    (net (code "38") (name "/NO_RELAY_2") (class "Default")
      (node (ref "P7") (pin "4") (pinfunction "4_4") (pintype "passive"))
      (node (ref "RELAY_2") (pin "3") (pinfunction "3_3") (pintype "passive"))
    )
    (net (code "39") (name "/NO_RELAY_3") (class "Default")
      (node (ref "P7") (pin "1") (pinfunction "1_1") (pintype "passive"))
      (node (ref "RELAY_3") (pin "3") (pinfunction "3_3") (pintype "passive"))
    )
    (net (code "40") (name "/NO_RELAY_4") (class "Default")
      (node (ref "P8") (pin "7") (pinfunction "7_7") (pintype "passive"))
      (node (ref "RELAY_4") (pin "3") (pinfunction "3_3") (pintype "passive"))
    )
    (net (code "41") (name "/NO_RELAY_5") (class "Default")
      (node (ref "P8") (pin "4") (pinfunction "4_4") (pintype "passive"))
      (node (ref "RELAY_5") (pin "3") (pinfunction "3_3") (pintype "passive"))
    )
    (net (code "42") (name "/NO_RELAY_6") (class "Default")
      (node (ref "P8") (pin "1") (pinfunction "1_1") (pintype "passive"))
      (node (ref "RELAY_6") (pin "3") (pinfunction "3_3") (pintype "passive"))
    )
    (net (code "43") (name "/NO_RELAY_7") (class "Default")
      (node (ref "P9") (pin "7") (pinfunction "7_7") (pintype "passive"))
      (node (ref "RELAY_7") (pin "3") (pinfunction "3_3") (pintype "passive"))
    )
    (net (code "44") (name "/NO_RELAY_8") (class "Default")
      (node (ref "P9") (pin "4") (pinfunction "4_4") (pintype "passive"))
      (node (ref "RELAY_8") (pin "3") (pinfunction "3_3") (pintype "passive"))
    )
    (net (code "45") (name "/NO_RELAY_9") (class "Default")
      (node (ref "P9") (pin "1") (pinfunction "1_1") (pintype "passive"))
      (node (ref "RELAY_9") (pin "3") (pinfunction "3_3") (pintype "passive"))
    )
    (net (code "46") (name "/NO_RELAY_10") (class "Default")
      (node (ref "P10") (pin "7") (pinfunction "7_7") (pintype "passive"))
      (node (ref "RELAY_10") (pin "3") (pinfunction "3_3") (pintype "passive"))
    )
    (net (code "47") (name "/NO_RELAY_11") (class "Default")
      (node (ref "P10") (pin "4") (pinfunction "4_4") (pintype "passive"))
      (node (ref "RELAY_11") (pin "3") (pinfunction "3_3") (pintype "passive"))
    )
    (net (code "48") (name "/NO_RELAY_12") (class "Default")
      (node (ref "P10") (pin "1") (pinfunction "1_1") (pintype "passive"))
      (node (ref "RELAY_12") (pin "3") (pinfunction "3_3") (pintype "passive"))
    )
    (net (code "49") (name "/NO_RELAY_13") (class "Default")
      (node (ref "P11") (pin "7") (pinfunction "7_7") (pintype "passive"))
      (node (ref "RELAY_13") (pin "3") (pinfunction "3_3") (pintype "passive"))
    )
    (net (code "50") (name "/NO_RELAY_14") (class "Default")
      (node (ref "P11") (pin "4") (pinfunction "4_4") (pintype "passive"))
      (node (ref "RELAY_14") (pin "3") (pinfunction "3_3") (pintype "passive"))
    )
    (net (code "51") (name "/NO_RELAY_15") (class "Default")
      (node (ref "P11") (pin "1") (pinfunction "1_1") (pintype "passive"))
      (node (ref "RELAY_15") (pin "3") (pinfunction "3_3") (pintype "passive"))
    )
    (net (code "52") (name "/NO_RELAY_16") (class "Default")
      (node (ref "P12") (pin "7") (pinfunction "7_7") (pintype "passive"))
      (node (ref "RELAY_16") (pin "3") (pinfunction "3_3") (pintype "passive"))
    )
    (net (code "53") (name "/NO_RELAY_17") (class "Default")
      (node (ref "P12") (pin "4") (pinfunction "4_4") (pintype "passive"))
      (node (ref "RELAY_17") (pin "3") (pinfunction "3_3") (pintype "passive"))
    )
    (net (code "54") (name "/NO_RELAY_18") (class "Default")
      (node (ref "P12") (pin "1") (pinfunction "1_1") (pintype "passive"))
      (node (ref "RELAY_18") (pin "3") (pinfunction "3_3") (pintype "passive"))
    )
    (net (code "55") (name "/SIG_COM_1") (class "Default")
      (node (ref "C1") (pin "2") (pinfunction "2_2") (pintype "passive"))
      (node (ref "C2") (pin "2") (pinfunction "2_2") (pintype "passive"))
      (node (ref "C3") (pin "2") (pinfunction "2_2") (pintype "passive"))
      (node (ref "D1") (pin "1") (pinfunction "A_1") (pintype "passive"))
      (node (ref "D2") (pin "1") (pinfunction "A_1") (pintype "passive"))
      (node (ref "D3") (pin "1") (pinfunction "A_1") (pintype "passive"))
      (node (ref "L1") (pin "2") (pinfunction "K_2") (pintype "passive"))
      (node (ref "L2") (pin "2") (pinfunction "K_2") (pintype "passive"))
      (node (ref "L3") (pin "2") (pinfunction "K_2") (pintype "passive"))
      (node (ref "P1") (pin "4") (pinfunction "4_4") (pintype "passive"))
      (node (ref "RELAY_1") (pin "2") (pinfunction "2_2") (pintype "passive"))
      (node (ref "RELAY_2") (pin "2") (pinfunction "2_2") (pintype "passive"))
      (node (ref "RELAY_3") (pin "2") (pinfunction "2_2") (pintype "passive"))
    )
    (net (code "56") (name "/SIG_COM_2") (class "Default")
      (node (ref "C4") (pin "2") (pinfunction "2_2") (pintype "passive"))
      (node (ref "C5") (pin "2") (pinfunction "2_2") (pintype "passive"))
      (node (ref "C6") (pin "2") (pinfunction "2_2") (pintype "passive"))
      (node (ref "D4") (pin "1") (pinfunction "A_1") (pintype "passive"))
      (node (ref "D5") (pin "1") (pinfunction "A_1") (pintype "passive"))
      (node (ref "D6") (pin "1") (pinfunction "A_1") (pintype "passive"))
      (node (ref "L4") (pin "2") (pinfunction "K_2") (pintype "passive"))
      (node (ref "L5") (pin "2") (pinfunction "K_2") (pintype "passive"))
      (node (ref "L6") (pin "2") (pinfunction "K_2") (pintype "passive"))
      (node (ref "P2") (pin "4") (pinfunction "4_4") (pintype "passive"))
      (node (ref "RELAY_4") (pin "2") (pinfunction "2_2") (pintype "passive"))
      (node (ref "RELAY_5") (pin "2") (pinfunction "2_2") (pintype "passive"))
      (node (ref "RELAY_6") (pin "2") (pinfunction "2_2") (pintype "passive"))
    )
    (net (code "57") (name "/SIG_COM_3") (class "Default")
      (node (ref "C7") (pin "2") (pinfunction "2_2") (pintype "passive"))
      (node (ref "C8") (pin "2") (pinfunction "2_2") (pintype "passive"))
      (node (ref "C9") (pin "2") (pinfunction "2_2") (pintype "passive"))
      (node (ref "D7") (pin "1") (pinfunction "A_1") (pintype "passive"))
      (node (ref "D8") (pin "1") (pinfunction "A_1") (pintype "passive"))
      (node (ref "D9") (pin "1") (pinfunction "A_1") (pintype "passive"))
      (node (ref "L7") (pin "2") (pinfunction "K_2") (pintype "passive"))
      (node (ref "L8") (pin "2") (pinfunction "K_2") (pintype "passive"))
      (node (ref "L9") (pin "2") (pinfunction "K_2") (pintype "passive"))
      (node (ref "P3") (pin "4") (pinfunction "4_4") (pintype "passive"))
      (node (ref "RELAY_7") (pin "2") (pinfunction "2_2") (pintype "passive"))
      (node (ref "RELAY_8") (pin "2") (pinfunction "2_2") (pintype "passive"))
      (node (ref "RELAY_9") (pin "2") (pinfunction "2_2") (pintype "passive"))
    )
    (net (code "58") (name "/SIG_COM_4") (class "Default")
      (node (ref "C10") (pin "2") (pinfunction "2_2") (pintype "passive"))
      (node (ref "C11") (pin "2") (pinfunction "2_2") (pintype "passive"))
      (node (ref "C12") (pin "2") (pinfunction "2_2") (pintype "passive"))
      (node (ref "D10") (pin "1") (pinfunction "A_1") (pintype "passive"))
      (node (ref "D11") (pin "1") (pinfunction "A_1") (pintype "passive"))
      (node (ref "D12") (pin "1") (pinfunction "A_1") (pintype "passive"))
      (node (ref "L10") (pin "2") (pinfunction "K_2") (pintype "passive"))
      (node (ref "L11") (pin "2") (pinfunction "K_2") (pintype "passive"))
      (node (ref "L12") (pin "2") (pinfunction "K_2") (pintype "passive"))
      (node (ref "P4") (pin "4") (pinfunction "4_4") (pintype "passive"))
      (node (ref "RELAY_10") (pin "2") (pinfunction "2_2") (pintype "passive"))
      (node (ref "RELAY_11") (pin "2") (pinfunction "2_2") (pintype "passive"))
      (node (ref "RELAY_12") (pin "2") (pinfunction "2_2") (pintype "passive"))
    )
    (net (code "59") (name "/SIG_COM_5") (class "Default")
      (node (ref "C13") (pin "2") (pinfunction "2_2") (pintype "passive"))
      (node (ref "C14") (pin "2") (pinfunction "2_2") (pintype "passive"))
      (node (ref "C15") (pin "2") (pinfunction "2_2") (pintype "passive"))
      (node (ref "D13") (pin "1") (pinfunction "A_1") (pintype "passive"))
      (node (ref "D14") (pin "1") (pinfunction "A_1") (pintype "passive"))
      (node (ref "D15") (pin "1") (pinfunction "A_1") (pintype "passive"))
      (node (ref "L13") (pin "2") (pinfunction "K_2") (pintype "passive"))
      (node (ref "L14") (pin "2") (pinfunction "K_2") (pintype "passive"))
      (node (ref "L15") (pin "2") (pinfunction "K_2") (pintype "passive"))
      (node (ref "P5") (pin "4") (pinfunction "4_4") (pintype "passive"))
      (node (ref "RELAY_13") (pin "2") (pinfunction "2_2") (pintype "passive"))
      (node (ref "RELAY_14") (pin "2") (pinfunction "2_2") (pintype "passive"))
      (node (ref "RELAY_15") (pin "2") (pinfunction "2_2") (pintype "passive"))
    )
    (net (code "60") (name "/SIG_COM_6") (class "Default")
      (node (ref "C16") (pin "2") (pinfunction "2_2") (pintype "passive"))
      (node (ref "C17") (pin "2") (pinfunction "2_2") (pintype "passive"))
      (node (ref "C18") (pin "2") (pinfunction "2_2") (pintype "passive"))
      (node (ref "D16") (pin "1") (pinfunction "A_1") (pintype "passive"))
      (node (ref "D17") (pin "1") (pinfunction "A_1") (pintype "passive"))
      (node (ref "D18") (pin "1") (pinfunction "A_1") (pintype "passive"))
      (node (ref "L16") (pin "2") (pinfunction "K_2") (pintype "passive"))
      (node (ref "L17") (pin "2") (pinfunction "K_2") (pintype "passive"))
      (node (ref "L18") (pin "2") (pinfunction "K_2") (pintype "passive"))
      (node (ref "P6") (pin "4") (pinfunction "4_4") (pintype "passive"))
      (node (ref "RELAY_16") (pin "2") (pinfunction "2_2") (pintype "passive"))
      (node (ref "RELAY_17") (pin "2") (pinfunction "2_2") (pintype "passive"))
      (node (ref "RELAY_18") (pin "2") (pinfunction "2_2") (pintype "passive"))
    )
    (net (code "61") (name "/SIG_IN_1") (class "Default")
      (node (ref "C1") (pin "1") (pinfunction "1_1") (pintype "passive"))
      (node (ref "D1") (pin "2") (pinfunction "K_2") (pintype "passive"))
      (node (ref "P1") (pin "1") (pinfunction "1_1") (pintype "passive"))
      (node (ref "R1") (pin "2") (pinfunction "2_2") (pintype "passive"))
      (node (ref "RELAY_1") (pin "1") (pinfunction "1_1") (pintype "passive"))
    )
    (net (code "62") (name "/SIG_IN_2") (class "Default")
      (node (ref "C2") (pin "1") (pinfunction "1_1") (pintype "passive"))
      (node (ref "D2") (pin "2") (pinfunction "K_2") (pintype "passive"))
      (node (ref "P1") (pin "2") (pinfunction "2_2") (pintype "passive"))
      (node (ref "R2") (pin "2") (pinfunction "2_2") (pintype "passive"))
      (node (ref "RELAY_2") (pin "1") (pinfunction "1_1") (pintype "passive"))
    )
    (net (code "63") (name "/SIG_IN_3") (class "Default")
      (node (ref "C3") (pin "1") (pinfunction "1_1") (pintype "passive"))
      (node (ref "D3") (pin "2") (pinfunction "K_2") (pintype "passive"))
      (node (ref "P1") (pin "3") (pinfunction "3_3") (pintype "passive"))
      (node (ref "R3") (pin "2") (pinfunction "2_2") (pintype "passive"))
      (node (ref "RELAY_3") (pin "1") (pinfunction "1_1") (pintype "passive"))
    )
    (net (code "64") (name "/SIG_IN_4") (class "Default")
      (node (ref "C4") (pin "1") (pinfunction "1_1") (pintype "passive"))
      (node (ref "D4") (pin "2") (pinfunction "K_2") (pintype "passive"))
      (node (ref "P2") (pin "1") (pinfunction "1_1") (pintype "passive"))
      (node (ref "R4") (pin "2") (pinfunction "2_2") (pintype "passive"))
      (node (ref "RELAY_4") (pin "1") (pinfunction "1_1") (pintype "passive"))
    )
    (net (code "65") (name "/SIG_IN_5") (class "Default")
      (node (ref "C5") (pin "1") (pinfunction "1_1") (pintype "passive"))
      (node (ref "D5") (pin "2") (pinfunction "K_2") (pintype "passive"))
      (node (ref "P2") (pin "2") (pinfunction "2_2") (pintype "passive"))
      (node (ref "R5") (pin "2") (pinfunction "2_2") (pintype "passive"))
      (node (ref "RELAY_5") (pin "1") (pinfunction "1_1") (pintype "passive"))
    )
    (net (code "66") (name "/SIG_IN_6") (class "Default")
      (node (ref "C6") (pin "1") (pinfunction "1_1") (pintype "passive"))
      (node (ref "D6") (pin "2") (pinfunction "K_2") (pintype "passive"))
      (node (ref "P2") (pin "3") (pinfunction "3_3") (pintype "passive"))
      (node (ref "R6") (pin "2") (pinfunction "2_2") (pintype "passive"))
      (node (ref "RELAY_6") (pin "1") (pinfunction "1_1") (pintype "passive"))
    )
    (net (code "67") (name "/SIG_IN_7") (class "Default")
      (node (ref "C7") (pin "1") (pinfunction "1_1") (pintype "passive"))
      (node (ref "D7") (pin "2") (pinfunction "K_2") (pintype "passive"))
      (node (ref "P3") (pin "1") (pinfunction "1_1") (pintype "passive"))
      (node (ref "R7") (pin "2") (pinfunction "2_2") (pintype "passive"))
      (node (ref "RELAY_7") (pin "1") (pinfunction "1_1") (pintype "passive"))
    )
    (net (code "68") (name "/SIG_IN_8") (class "Default")
      (node (ref "C8") (pin "1") (pinfunction "1_1") (pintype "passive"))
      (node (ref "D8") (pin "2") (pinfunction "K_2") (pintype "passive"))
      (node (ref "P3") (pin "2") (pinfunction "2_2") (pintype "passive"))
      (node (ref "R8") (pin "2") (pinfunction "2_2") (pintype "passive"))
      (node (ref "RELAY_8") (pin "1") (pinfunction "1_1") (pintype "passive"))
    )
    (net (code "69") (name "/SIG_IN_9") (class "Default")
      (node (ref "C9") (pin "1") (pinfunction "1_1") (pintype "passive"))
      (node (ref "D9") (pin "2") (pinfunction "K_2") (pintype "passive"))
      (node (ref "P3") (pin "3") (pinfunction "3_3") (pintype "passive"))
      (node (ref "R9") (pin "2") (pinfunction "2_2") (pintype "passive"))
      (node (ref "RELAY_9") (pin "1") (pinfunction "1_1") (pintype "passive"))
    )
    (net (code "70") (name "/SIG_IN_10") (class "Default")
      (node (ref "C10") (pin "1") (pinfunction "1_1") (pintype "passive"))
      (node (ref "D10") (pin "2") (pinfunction "K_2") (pintype "passive"))
      (node (ref "P4") (pin "1") (pinfunction "1_1") (pintype "passive"))
      (node (ref "R10") (pin "2") (pinfunction "2_2") (pintype "passive"))
      (node (ref "RELAY_10") (pin "1") (pinfunction "1_1") (pintype "passive"))
    )
    (net (code "71") (name "/SIG_IN_11") (class "Default")
      (node (ref "C11") (pin "1") (pinfunction "1_1") (pintype "passive"))
      (node (ref "D11") (pin "2") (pinfunction "K_2") (pintype "passive"))
      (node (ref "P4") (pin "2") (pinfunction "2_2") (pintype "passive"))
      (node (ref "R11") (pin "2") (pinfunction "2_2") (pintype "passive"))
      (node (ref "RELAY_11") (pin "1") (pinfunction "1_1") (pintype "passive"))
    )
    (net (code "72") (name "/SIG_IN_12") (class "Default")
      (node (ref "C12") (pin "1") (pinfunction "1_1") (pintype "passive"))
      (node (ref "D12") (pin "2") (pinfunction "K_2") (pintype "passive"))
      (node (ref "P4") (pin "3") (pinfunction "3_3") (pintype "passive"))
      (node (ref "R12") (pin "2") (pinfunction "2_2") (pintype "passive"))
      (node (ref "RELAY_12") (pin "1") (pinfunction "1_1") (pintype "passive"))
    )
    (net (code "73") (name "/SIG_IN_13") (class "Default")
      (node (ref "C13") (pin "1") (pinfunction "1_1") (pintype "passive"))
      (node (ref "D13") (pin "2") (pinfunction "K_2") (pintype "passive"))
      (node (ref "P5") (pin "1") (pinfunction "1_1") (pintype "passive"))
      (node (ref "R13") (pin "2") (pinfunction "2_2") (pintype "passive"))
      (node (ref "RELAY_13") (pin "1") (pinfunction "1_1") (pintype "passive"))
    )
    (net (code "74") (name "/SIG_IN_14") (class "Default")
      (node (ref "C14") (pin "1") (pinfunction "1_1") (pintype "passive"))
      (node (ref "D14") (pin "2") (pinfunction "K_2") (pintype "passive"))
      (node (ref "P5") (pin "2") (pinfunction "2_2") (pintype "passive"))
      (node (ref "R14") (pin "2") (pinfunction "2_2") (pintype "passive"))
      (node (ref "RELAY_14") (pin "1") (pinfunction "1_1") (pintype "passive"))
    )
    (net (code "75") (name "/SIG_IN_15") (class "Default")
      (node (ref "C15") (pin "1") (pinfunction "1_1") (pintype "passive"))
      (node (ref "D15") (pin "2") (pinfunction "K_2") (pintype "passive"))
      (node (ref "P5") (pin "3") (pinfunction "3_3") (pintype "passive"))
      (node (ref "R15") (pin "2") (pinfunction "2_2") (pintype "passive"))
      (node (ref "RELAY_15") (pin "1") (pinfunction "1_1") (pintype "passive"))
    )
    (net (code "76") (name "/SIG_IN_16") (class "Default")
      (node (ref "C16") (pin "1") (pinfunction "1_1") (pintype "passive"))
      (node (ref "D16") (pin "2") (pinfunction "K_2") (pintype "passive"))
      (node (ref "P6") (pin "1") (pinfunction "1_1") (pintype "passive"))
      (node (ref "R16") (pin "2") (pinfunction "2_2") (pintype "passive"))
      (node (ref "RELAY_16") (pin "1") (pinfunction "1_1") (pintype "passive"))
    )
    (net (code "77") (name "/SIG_IN_17") (class "Default")
      (node (ref "C17") (pin "1") (pinfunction "1_1") (pintype "passive"))
      (node (ref "D17") (pin "2") (pinfunction "K_2") (pintype "passive"))
      (node (ref "P6") (pin "2") (pinfunction "2_2") (pintype "passive"))
      (node (ref "R17") (pin "2") (pinfunction "2_2") (pintype "passive"))
      (node (ref "RELAY_17") (pin "1") (pinfunction "1_1") (pintype "passive"))
    )
    (net (code "78") (name "/SIG_IN_18") (class "Default")
      (node (ref "C18") (pin "1") (pinfunction "1_1") (pintype "passive"))
      (node (ref "D18") (pin "2") (pinfunction "K_2") (pintype "passive"))
      (node (ref "P6") (pin "3") (pinfunction "3_3") (pintype "passive"))
      (node (ref "R18") (pin "2") (pinfunction "2_2") (pintype "passive"))
      (node (ref "RELAY_18") (pin "1") (pinfunction "1_1") (pintype "passive"))
    )
    (net (code "79") (name "Net-(L1-A)") (class "Default")
      (node (ref "L1") (pin "1") (pinfunction "A_1") (pintype "passive"))
      (node (ref "R1") (pin "1") (pinfunction "1_1") (pintype "passive"))
    )
    (net (code "80") (name "Net-(L2-A)") (class "Default")
      (node (ref "L2") (pin "1") (pinfunction "A_1") (pintype "passive"))
      (node (ref "R2") (pin "1") (pinfunction "1_1") (pintype "passive"))
    )
    (net (code "81") (name "Net-(L3-A)") (class "Default")
      (node (ref "L3") (pin "1") (pinfunction "A_1") (pintype "passive"))
      (node (ref "R3") (pin "1") (pinfunction "1_1") (pintype "passive"))
    )
    (net (code "82") (name "Net-(L4-A)") (class "Default")
      (node (ref "L4") (pin "1") (pinfunction "A_1") (pintype "passive"))
      (node (ref "R4") (pin "1") (pinfunction "1_1") (pintype "passive"))
    )
    (net (code "83") (name "Net-(L5-A)") (class "Default")
      (node (ref "L5") (pin "1") (pinfunction "A_1") (pintype "passive"))
      (node (ref "R5") (pin "1") (pinfunction "1_1") (pintype "passive"))
    )
    (net (code "84") (name "Net-(L6-A)") (class "Default")
      (node (ref "L6") (pin "1") (pinfunction "A_1") (pintype "passive"))
      (node (ref "R6") (pin "1") (pinfunction "1_1") (pintype "passive"))
    )
    (net (code "85") (name "Net-(L7-A)") (class "Default")
      (node (ref "L7") (pin "1") (pinfunction "A_1") (pintype "passive"))
      (node (ref "R7") (pin "1") (pinfunction "1_1") (pintype "passive"))
    )
    (net (code "86") (name "Net-(L8-A)") (class "Default")
      (node (ref "L8") (pin "1") (pinfunction "A_1") (pintype "passive"))
      (node (ref "R8") (pin "1") (pinfunction "1_1") (pintype "passive"))
    )
    (net (code "87") (name "Net-(L9-A)") (class "Default")
      (node (ref "L9") (pin "1") (pinfunction "A_1") (pintype "passive"))
      (node (ref "R9") (pin "1") (pinfunction "1_1") (pintype "passive"))
    )
    (net (code "88") (name "Net-(L10-A)") (class "Default")
      (node (ref "L10") (pin "1") (pinfunction "A_1") (pintype "passive"))
      (node (ref "R10") (pin "1") (pinfunction "1_1") (pintype "passive"))
    )
    (net (code "89") (name "Net-(L11-A)") (class "Default")
      (node (ref "L11") (pin "1") (pinfunction "A_1") (pintype "passive"))
      (node (ref "R11") (pin "1") (pinfunction "1_1") (pintype "passive"))
    )
    (net (code "90") (name "Net-(L12-A)") (class "Default")
      (node (ref "L12") (pin "1") (pinfunction "A_1") (pintype "passive"))
      (node (ref "R12") (pin "1") (pinfunction "1_1") (pintype "passive"))
    )
    (net (code "91") (name "Net-(L13-A)") (class "Default")
      (node (ref "L13") (pin "1") (pinfunction "A_1") (pintype "passive"))
      (node (ref "R13") (pin "1") (pinfunction "1_1") (pintype "passive"))
    )
    (net (code "92") (name "Net-(L14-A)") (class "Default")
      (node (ref "L14") (pin "1") (pinfunction "A_1") (pintype "passive"))
      (node (ref "R14") (pin "1") (pinfunction "1_1") (pintype "passive"))
    )
    (net (code "93") (name "Net-(L15-A)") (class "Default")
      (node (ref "L15") (pin "1") (pinfunction "A_1") (pintype "passive"))
      (node (ref "R15") (pin "1") (pinfunction "1_1") (pintype "passive"))
    )
    (net (code "94") (name "Net-(L16-A)") (class "Default")
      (node (ref "L16") (pin "1") (pinfunction "A_1") (pintype "passive"))
      (node (ref "R16") (pin "1") (pinfunction "1_1") (pintype "passive"))
    )
    (net (code "95") (name "Net-(L17-A)") (class "Default")
      (node (ref "L17") (pin "1") (pinfunction "A_1") (pintype "passive"))
      (node (ref "R17") (pin "1") (pinfunction "1_1") (pintype "passive"))
    )
    (net (code "96") (name "Net-(L18-A)") (class "Default")
      (node (ref "L18") (pin "1") (pinfunction "A_1") (pintype "passive"))
      (node (ref "R18") (pin "1") (pinfunction "1_1") (pintype "passive"))
    )
    (net (code "97") (name "unconnected-(1-Pad1)") (class "Default")
      (node (ref "1") (pin "1") (pinfunction "1_1") (pintype "passive"))
    )
    (net (code "98") (name "unconnected-(2-Pad1)") (class "Default")
      (node (ref "2") (pin "1") (pinfunction "1_1") (pintype "passive"))
    )
    (net (code "99") (name "unconnected-(3-Pad1)") (class "Default")
      (node (ref "3") (pin "1") (pinfunction "1_1") (pintype "passive"))
    )
    (net (code "100") (name "unconnected-(4-Pad1)") (class "Default")
      (node (ref "4") (pin "1") (pinfunction "1_1") (pintype "passive"))
    )
    (net (code "101") (name "unconnected-(5-Pad1)") (class "Default")
      (node (ref "5") (pin "1") (pinfunction "1_1") (pintype "passive"))
    )
    (net (code "102") (name "unconnected-(6-Pad1)") (class "Default")
      (node (ref "6") (pin "1") (pinfunction "1_1") (pintype "passive"))
    )
    (net (code "103") (name "unconnected-(7-Pad1)") (class "Default")
      (node (ref "7") (pin "1") (pinfunction "1_1") (pintype "passive"))
    )
    (net (code "104") (name "unconnected-(8-Pad1)") (class "Default")
      (node (ref "8") (pin "1") (pinfunction "1_1") (pintype "passive"))
    )
  )
)
